# Drivers.net
KiCad netlist of a schematic drawn in Altium Designer
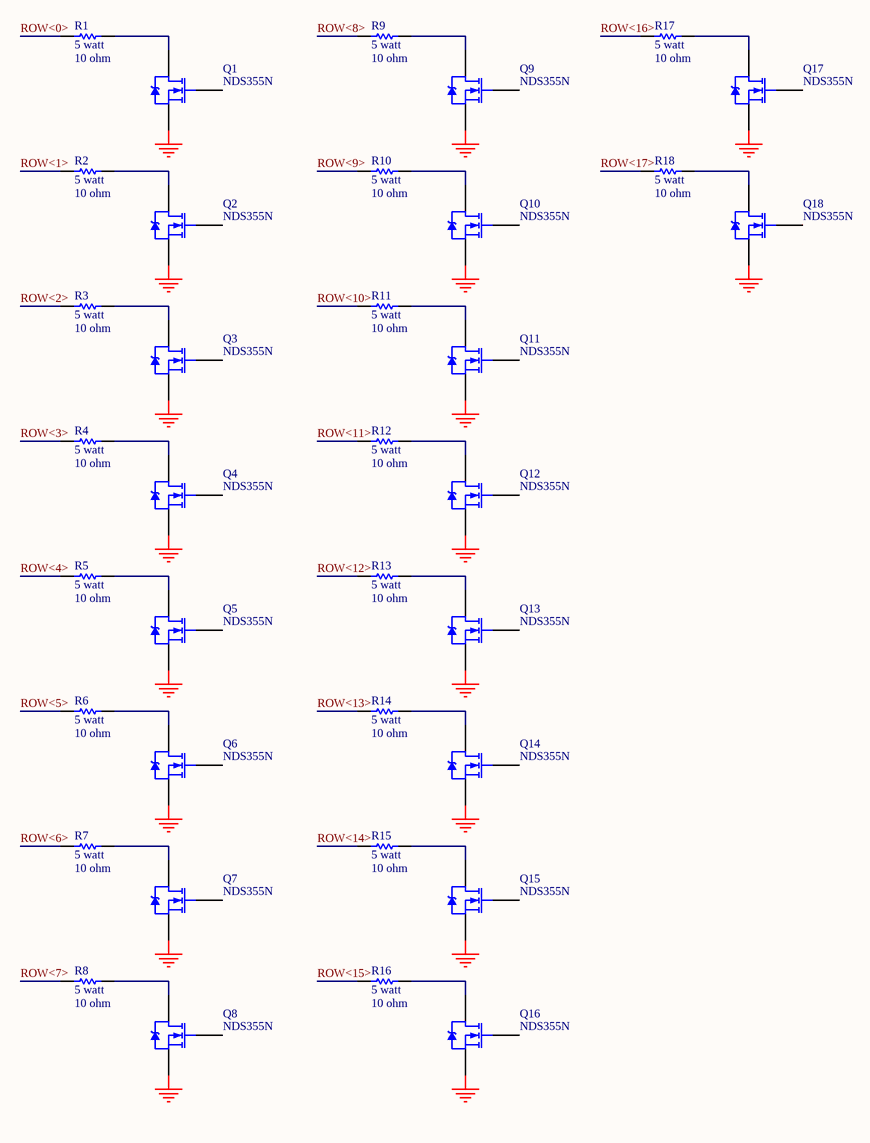
[diagram p0: Drivers.SchDoc]

(export (version "E")
  (design (tool "Eeschema 10.0.6"))
  (components
    (comp (ref "Q1")
      (value "NDS355N")
      (footprint "SO-G3")
      (description "N-Channel Logic Level Enhancement Mode FET")
      (fields (field (name "MANUFACTURER") "Fairchild"))
      (libsource (lib "Schlib1") (part "NDS355N"))
    )
    (comp (ref "Q2")
      (value "NDS355N")
      (footprint "SO-G3")
      (description "N-Channel Logic Level Enhancement Mode FET")
      (fields (field (name "MANUFACTURER") "Fairchild"))
      (libsource (lib "Schlib1") (part "NDS355N"))
    )
    (comp (ref "Q3")
      (value "NDS355N")
      (footprint "SO-G3")
      (description "N-Channel Logic Level Enhancement Mode FET")
      (fields (field (name "MANUFACTURER") "Fairchild"))
      (libsource (lib "Schlib1") (part "NDS355N"))
    )
    (comp (ref "Q4")
      (value "NDS355N")
      (footprint "SO-G3")
      (description "N-Channel Logic Level Enhancement Mode FET")
      (fields (field (name "MANUFACTURER") "Fairchild"))
      (libsource (lib "Schlib1") (part "NDS355N"))
    )
    (comp (ref "Q5")
      (value "NDS355N")
      (footprint "SO-G3")
      (description "N-Channel Logic Level Enhancement Mode FET")
      (fields (field (name "MANUFACTURER") "Fairchild"))
      (libsource (lib "Schlib1") (part "NDS355N"))
    )
    (comp (ref "Q6")
      (value "NDS355N")
      (footprint "SO-G3")
      (description "N-Channel Logic Level Enhancement Mode FET")
      (fields (field (name "MANUFACTURER") "Fairchild"))
      (libsource (lib "Schlib1") (part "NDS355N"))
    )
    (comp (ref "Q7")
      (value "NDS355N")
      (footprint "SO-G3")
      (description "N-Channel Logic Level Enhancement Mode FET")
      (fields (field (name "MANUFACTURER") "Fairchild"))
      (libsource (lib "Schlib1") (part "NDS355N"))
    )
    (comp (ref "Q8")
      (value "NDS355N")
      (footprint "SO-G3")
      (description "N-Channel Logic Level Enhancement Mode FET")
      (fields (field (name "MANUFACTURER") "Fairchild"))
      (libsource (lib "Schlib1") (part "NDS355N"))
    )
    (comp (ref "Q9")
      (value "NDS355N")
      (footprint "SO-G3")
      (description "N-Channel Logic Level Enhancement Mode FET")
      (fields (field (name "MANUFACTURER") "Fairchild"))
      (libsource (lib "Schlib1") (part "NDS355N"))
    )
    (comp (ref "Q10")
      (value "NDS355N")
      (footprint "SO-G3")
      (description "N-Channel Logic Level Enhancement Mode FET")
      (fields (field (name "MANUFACTURER") "Fairchild"))
      (libsource (lib "Schlib1") (part "NDS355N"))
    )
    (comp (ref "Q11")
      (value "NDS355N")
      (footprint "SO-G3")
      (description "N-Channel Logic Level Enhancement Mode FET")
      (fields (field (name "MANUFACTURER") "Fairchild"))
      (libsource (lib "Schlib1") (part "NDS355N"))
    )
    (comp (ref "Q12")
      (value "NDS355N")
      (footprint "SO-G3")
      (description "N-Channel Logic Level Enhancement Mode FET")
      (fields (field (name "MANUFACTURER") "Fairchild"))
      (libsource (lib "Schlib1") (part "NDS355N"))
    )
    (comp (ref "Q13")
      (value "NDS355N")
      (footprint "SO-G3")
      (description "N-Channel Logic Level Enhancement Mode FET")
      (fields (field (name "MANUFACTURER") "Fairchild"))
      (libsource (lib "Schlib1") (part "NDS355N"))
    )
    (comp (ref "Q14")
      (value "NDS355N")
      (footprint "SO-G3")
      (description "N-Channel Logic Level Enhancement Mode FET")
      (fields (field (name "MANUFACTURER") "Fairchild"))
      (libsource (lib "Schlib1") (part "NDS355N"))
    )
    (comp (ref "Q15")
      (value "NDS355N")
      (footprint "SO-G3")
      (description "N-Channel Logic Level Enhancement Mode FET")
      (fields (field (name "MANUFACTURER") "Fairchild"))
      (libsource (lib "Schlib1") (part "NDS355N"))
    )
    (comp (ref "Q16")
      (value "NDS355N")
      (footprint "SO-G3")
      (description "N-Channel Logic Level Enhancement Mode FET")
      (fields (field (name "MANUFACTURER") "Fairchild"))
      (libsource (lib "Schlib1") (part "NDS355N"))
    )
    (comp (ref "Q17")
      (value "NDS355N")
      (footprint "SO-G3")
      (description "N-Channel Logic Level Enhancement Mode FET")
      (fields (field (name "MANUFACTURER") "Fairchild"))
      (libsource (lib "Schlib1") (part "NDS355N"))
    )
    (comp (ref "Q18")
      (value "NDS355N")
      (footprint "SO-G3")
      (description "N-Channel Logic Level Enhancement Mode FET")
      (fields (field (name "MANUFACTURER") "Fairchild"))
      (libsource (lib "Schlib1") (part "NDS355N"))
    )
    (comp (ref "R1")
      (value "5 watt")
      (footprint "AXIAL-1.0")
      (description "Resistor")
      (fields
        (field (name "MANUFACTURER") "Generic Components")
        (field (name "ALTIUM_VALUE") "10 ohm")
        (field (name "PUBLISHER") "Altium Limited")
      )
      (libsource (lib "Miscellaneous Devices") (part "Res1"))
    )
    (comp (ref "R2")
      (value "5 watt")
      (footprint "AXIAL-1.0")
      (description "Resistor")
      (fields
        (field (name "MANUFACTURER") "Generic Components")
        (field (name "ALTIUM_VALUE") "10 ohm")
        (field (name "PUBLISHER") "Altium Limited")
      )
      (libsource (lib "Miscellaneous Devices") (part "Res1"))
    )
    (comp (ref "R3")
      (value "5 watt")
      (footprint "AXIAL-1.0")
      (description "Resistor")
      (fields
        (field (name "MANUFACTURER") "Generic Components")
        (field (name "ALTIUM_VALUE") "10 ohm")
        (field (name "PUBLISHER") "Altium Limited")
      )
      (libsource (lib "Miscellaneous Devices") (part "Res1"))
    )
    (comp (ref "R4")
      (value "5 watt")
      (footprint "AXIAL-1.0")
      (description "Resistor")
      (fields
        (field (name "MANUFACTURER") "Generic Components")
        (field (name "ALTIUM_VALUE") "10 ohm")
        (field (name "PUBLISHER") "Altium Limited")
      )
      (libsource (lib "Miscellaneous Devices") (part "Res1"))
    )
    (comp (ref "R5")
      (value "5 watt")
      (footprint "AXIAL-1.0")
      (description "Resistor")
      (fields
        (field (name "MANUFACTURER") "Generic Components")
        (field (name "ALTIUM_VALUE") "10 ohm")
        (field (name "PUBLISHER") "Altium Limited")
      )
      (libsource (lib "Miscellaneous Devices") (part "Res1"))
    )
    (comp (ref "R6")
      (value "5 watt")
      (footprint "AXIAL-1.0")
      (description "Resistor")
      (fields
        (field (name "MANUFACTURER") "Generic Components")
        (field (name "ALTIUM_VALUE") "10 ohm")
        (field (name "PUBLISHER") "Altium Limited")
      )
      (libsource (lib "Miscellaneous Devices") (part "Res1"))
    )
    (comp (ref "R7")
      (value "5 watt")
      (footprint "AXIAL-1.0")
      (description "Resistor")
      (fields
        (field (name "MANUFACTURER") "Generic Components")
        (field (name "ALTIUM_VALUE") "10 ohm")
        (field (name "PUBLISHER") "Altium Limited")
      )
      (libsource (lib "Miscellaneous Devices") (part "Res1"))
    )
    (comp (ref "R8")
      (value "5 watt")
      (footprint "AXIAL-1.0")
      (description "Resistor")
      (fields
        (field (name "MANUFACTURER") "Generic Components")
        (field (name "ALTIUM_VALUE") "10 ohm")
        (field (name "PUBLISHER") "Altium Limited")
      )
      (libsource (lib "Miscellaneous Devices") (part "Res1"))
    )
    (comp (ref "R9")
      (value "5 watt")
      (footprint "AXIAL-1.0")
      (description "Resistor")
      (fields
        (field (name "MANUFACTURER") "Generic Components")
        (field (name "ALTIUM_VALUE") "10 ohm")
        (field (name "PUBLISHER") "Altium Limited")
      )
      (libsource (lib "Miscellaneous Devices") (part "Res1"))
    )
    (comp (ref "R10")
      (value "5 watt")
      (footprint "AXIAL-1.0")
      (description "Resistor")
      (fields
        (field (name "MANUFACTURER") "Generic Components")
        (field (name "ALTIUM_VALUE") "10 ohm")
        (field (name "PUBLISHER") "Altium Limited")
      )
      (libsource (lib "Miscellaneous Devices") (part "Res1"))
    )
    (comp (ref "R11")
      (value "5 watt")
      (footprint "AXIAL-1.0")
      (description "Resistor")
      (fields
        (field (name "MANUFACTURER") "Generic Components")
        (field (name "ALTIUM_VALUE") "10 ohm")
        (field (name "PUBLISHER") "Altium Limited")
      )
      (libsource (lib "Miscellaneous Devices") (part "Res1"))
    )
    (comp (ref "R12")
      (value "5 watt")
      (footprint "AXIAL-1.0")
      (description "Resistor")
      (fields
        (field (name "MANUFACTURER") "Generic Components")
        (field (name "ALTIUM_VALUE") "10 ohm")
        (field (name "PUBLISHER") "Altium Limited")
      )
      (libsource (lib "Miscellaneous Devices") (part "Res1"))
    )
    (comp (ref "R13")
      (value "5 watt")
      (footprint "AXIAL-1.0")
      (description "Resistor")
      (fields
        (field (name "MANUFACTURER") "Generic Components")
        (field (name "ALTIUM_VALUE") "10 ohm")
        (field (name "PUBLISHER") "Altium Limited")
      )
      (libsource (lib "Miscellaneous Devices") (part "Res1"))
    )
    (comp (ref "R14")
      (value "5 watt")
      (footprint "AXIAL-1.0")
      (description "Resistor")
      (fields
        (field (name "MANUFACTURER") "Generic Components")
        (field (name "ALTIUM_VALUE") "10 ohm")
        (field (name "PUBLISHER") "Altium Limited")
      )
      (libsource (lib "Miscellaneous Devices") (part "Res1"))
    )
    (comp (ref "R15")
      (value "5 watt")
      (footprint "AXIAL-1.0")
      (description "Resistor")
      (fields
        (field (name "MANUFACTURER") "Generic Components")
        (field (name "ALTIUM_VALUE") "10 ohm")
        (field (name "PUBLISHER") "Altium Limited")
      )
      (libsource (lib "Miscellaneous Devices") (part "Res1"))
    )
    (comp (ref "R16")
      (value "5 watt")
      (footprint "AXIAL-1.0")
      (description "Resistor")
      (fields
        (field (name "MANUFACTURER") "Generic Components")
        (field (name "ALTIUM_VALUE") "10 ohm")
        (field (name "PUBLISHER") "Altium Limited")
      )
      (libsource (lib "Miscellaneous Devices") (part "Res1"))
    )
    (comp (ref "R17")
      (value "5 watt")
      (footprint "AXIAL-1.0")
      (description "Resistor")
      (fields
        (field (name "MANUFACTURER") "Generic Components")
        (field (name "ALTIUM_VALUE") "10 ohm")
        (field (name "PUBLISHER") "Altium Limited")
      )
      (libsource (lib "Miscellaneous Devices") (part "Res1"))
    )
    (comp (ref "R18")
      (value "5 watt")
      (footprint "AXIAL-1.0")
      (description "Resistor")
      (fields
        (field (name "MANUFACTURER") "Generic Components")
        (field (name "ALTIUM_VALUE") "10 ohm")
        (field (name "PUBLISHER") "Altium Limited")
      )
      (libsource (lib "Miscellaneous Devices") (part "Res1"))
    )
  )
  (nets
    (net (code "1") (name "/ROW<0>") (class "Default")
      (node (ref "R1") (pin "1") (pinfunction "1_1") (pintype "passive"))
    )
    (net (code "2") (name "/ROW<1>") (class "Default")
      (node (ref "R2") (pin "1") (pinfunction "1_1") (pintype "passive"))
    )
    (net (code "3") (name "/ROW<2>") (class "Default")
      (node (ref "R3") (pin "1") (pinfunction "1_1") (pintype "passive"))
    )
    (net (code "4") (name "/ROW<3>") (class "Default")
      (node (ref "R4") (pin "1") (pinfunction "1_1") (pintype "passive"))
    )
    (net (code "5") (name "/ROW<4>") (class "Default")
      (node (ref "R5") (pin "1") (pinfunction "1_1") (pintype "passive"))
    )
    (net (code "6") (name "/ROW<5>") (class "Default")
      (node (ref "R6") (pin "1") (pinfunction "1_1") (pintype "passive"))
    )
    (net (code "7") (name "/ROW<6>") (class "Default")
      (node (ref "R7") (pin "1") (pinfunction "1_1") (pintype "passive"))
    )
    (net (code "8") (name "/ROW<7>") (class "Default")
      (node (ref "R8") (pin "1") (pinfunction "1_1") (pintype "passive"))
    )
    (net (code "9") (name "/ROW<8>") (class "Default")
      (node (ref "R9") (pin "1") (pinfunction "1_1") (pintype "passive"))
    )
    (net (code "10") (name "/ROW<9>") (class "Default")
      (node (ref "R10") (pin "1") (pinfunction "1_1") (pintype "passive"))
    )
    (net (code "11") (name "/ROW<10>") (class "Default")
      (node (ref "R11") (pin "1") (pinfunction "1_1") (pintype "passive"))
    )
    (net (code "12") (name "/ROW<11>") (class "Default")
      (node (ref "R12") (pin "1") (pinfunction "1_1") (pintype "passive"))
    )
    (net (code "13") (name "/ROW<12>") (class "Default")
      (node (ref "R13") (pin "1") (pinfunction "1_1") (pintype "passive"))
    )
    (net (code "14") (name "/ROW<13>") (class "Default")
      (node (ref "R14") (pin "1") (pinfunction "1_1") (pintype "passive"))
    )
    (net (code "15") (name "/ROW<14>") (class "Default")
      (node (ref "R15") (pin "1") (pinfunction "1_1") (pintype "passive"))
    )
    (net (code "16") (name "/ROW<15>") (class "Default")
      (node (ref "R16") (pin "1") (pinfunction "1_1") (pintype "passive"))
    )
    (net (code "17") (name "/ROW<16>") (class "Default")
      (node (ref "R17") (pin "1") (pinfunction "1_1") (pintype "passive"))
    )
    (net (code "18") (name "/ROW<17>") (class "Default")
      (node (ref "R18") (pin "1") (pinfunction "1_1") (pintype "passive"))
    )
    (net (code "19") (name "GND") (class "Default")
      (node (ref "Q1") (pin "2") (pinfunction "S_2") (pintype "passive"))
      (node (ref "Q10") (pin "2") (pinfunction "S_2") (pintype "passive"))
      (node (ref "Q11") (pin "2") (pinfunction "S_2") (pintype "passive"))
      (node (ref "Q12") (pin "2") (pinfunction "S_2") (pintype "passive"))
      (node (ref "Q13") (pin "2") (pinfunction "S_2") (pintype "passive"))
      (node (ref "Q14") (pin "2") (pinfunction "S_2") (pintype "passive"))
      (node (ref "Q15") (pin "2") (pinfunction "S_2") (pintype "passive"))
      (node (ref "Q16") (pin "2") (pinfunction "S_2") (pintype "passive"))
      (node (ref "Q17") (pin "2") (pinfunction "S_2") (pintype "passive"))
      (node (ref "Q18") (pin "2") (pinfunction "S_2") (pintype "passive"))
      (node (ref "Q2") (pin "2") (pinfunction "S_2") (pintype "passive"))
      (node (ref "Q3") (pin "2") (pinfunction "S_2") (pintype "passive"))
      (node (ref "Q4") (pin "2") (pinfunction "S_2") (pintype "passive"))
      (node (ref "Q5") (pin "2") (pinfunction "S_2") (pintype "passive"))
      (node (ref "Q6") (pin "2") (pinfunction "S_2") (pintype "passive"))
      (node (ref "Q7") (pin "2") (pinfunction "S_2") (pintype "passive"))
      (node (ref "Q8") (pin "2") (pinfunction "S_2") (pintype "passive"))
      (node (ref "Q9") (pin "2") (pinfunction "S_2") (pintype "passive"))
    )
    (net (code "20") (name "Net-(Q1-D)") (class "Default")
      (node (ref "Q1") (pin "3") (pinfunction "D_3") (pintype "passive"))
      (node (ref "R1") (pin "2") (pinfunction "2_2") (pintype "passive"))
    )
    (net (code "21") (name "Net-(Q2-D)") (class "Default")
      (node (ref "Q2") (pin "3") (pinfunction "D_3") (pintype "passive"))
      (node (ref "R2") (pin "2") (pinfunction "2_2") (pintype "passive"))
    )
    (net (code "22") (name "Net-(Q3-D)") (class "Default")
      (node (ref "Q3") (pin "3") (pinfunction "D_3") (pintype "passive"))
      (node (ref "R3") (pin "2") (pinfunction "2_2") (pintype "passive"))
    )
    (net (code "23") (name "Net-(Q4-D)") (class "Default")
      (node (ref "Q4") (pin "3") (pinfunction "D_3") (pintype "passive"))
      (node (ref "R4") (pin "2") (pinfunction "2_2") (pintype "passive"))
    )
    (net (code "24") (name "Net-(Q5-D)") (class "Default")
      (node (ref "Q5") (pin "3") (pinfunction "D_3") (pintype "passive"))
      (node (ref "R5") (pin "2") (pinfunction "2_2") (pintype "passive"))
    )
    (net (code "25") (name "Net-(Q6-D)") (class "Default")
      (node (ref "Q6") (pin "3") (pinfunction "D_3") (pintype "passive"))
      (node (ref "R6") (pin "2") (pinfunction "2_2") (pintype "passive"))
    )
    (net (code "26") (name "Net-(Q7-D)") (class "Default")
      (node (ref "Q7") (pin "3") (pinfunction "D_3") (pintype "passive"))
      (node (ref "R7") (pin "2") (pinfunction "2_2") (pintype "passive"))
    )
    (net (code "27") (name "Net-(Q8-D)") (class "Default")
      (node (ref "Q8") (pin "3") (pinfunction "D_3") (pintype "passive"))
      (node (ref "R8") (pin "2") (pinfunction "2_2") (pintype "passive"))
    )
    (net (code "28") (name "Net-(Q9-D)") (class "Default")
      (node (ref "Q9") (pin "3") (pinfunction "D_3") (pintype "passive"))
      (node (ref "R9") (pin "2") (pinfunction "2_2") (pintype "passive"))
    )
    (net (code "29") (name "Net-(Q10-D)") (class "Default")
      (node (ref "Q10") (pin "3") (pinfunction "D_3") (pintype "passive"))
      (node (ref "R10") (pin "2") (pinfunction "2_2") (pintype "passive"))
    )
    (net (code "30") (name "Net-(Q11-D)") (class "Default")
      (node (ref "Q11") (pin "3") (pinfunction "D_3") (pintype "passive"))
      (node (ref "R11") (pin "2") (pinfunction "2_2") (pintype "passive"))
    )
    (net (code "31") (name "Net-(Q12-D)") (class "Default")
      (node (ref "Q12") (pin "3") (pinfunction "D_3") (pintype "passive"))
      (node (ref "R12") (pin "2") (pinfunction "2_2") (pintype "passive"))
    )
    (net (code "32") (name "Net-(Q13-D)") (class "Default")
      (node (ref "Q13") (pin "3") (pinfunction "D_3") (pintype "passive"))
      (node (ref "R13") (pin "2") (pinfunction "2_2") (pintype "passive"))
    )
    (net (code "33") (name "Net-(Q14-D)") (class "Default")
      (node (ref "Q14") (pin "3") (pinfunction "D_3") (pintype "passive"))
      (node (ref "R14") (pin "2") (pinfunction "2_2") (pintype "passive"))
    )
    (net (code "34") (name "Net-(Q15-D)") (class "Default")
      (node (ref "Q15") (pin "3") (pinfunction "D_3") (pintype "passive"))
      (node (ref "R15") (pin "2") (pinfunction "2_2") (pintype "passive"))
    )
    (net (code "35") (name "Net-(Q16-D)") (class "Default")
      (node (ref "Q16") (pin "3") (pinfunction "D_3") (pintype "passive"))
      (node (ref "R16") (pin "2") (pinfunction "2_2") (pintype "passive"))
    )
    (net (code "36") (name "Net-(Q17-D)") (class "Default")
      (node (ref "Q17") (pin "3") (pinfunction "D_3") (pintype "passive"))
      (node (ref "R17") (pin "2") (pinfunction "2_2") (pintype "passive"))
    )
    (net (code "37") (name "Net-(Q18-D)") (class "Default")
      (node (ref "Q18") (pin "3") (pinfunction "D_3") (pintype "passive"))
      (node (ref "R18") (pin "2") (pinfunction "2_2") (pintype "passive"))
    )
    (net (code "38") (name "unconnected-(Q1-G-Pad1)") (class "Default")
      (node (ref "Q1") (pin "1") (pinfunction "G_1") (pintype "passive"))
    )
    (net (code "39") (name "unconnected-(Q2-G-Pad1)") (class "Default")
      (node (ref "Q2") (pin "1") (pinfunction "G_1") (pintype "passive"))
    )
    (net (code "40") (name "unconnected-(Q3-G-Pad1)") (class "Default")
      (node (ref "Q3") (pin "1") (pinfunction "G_1") (pintype "passive"))
    )
    (net (code "41") (name "unconnected-(Q4-G-Pad1)") (class "Default")
      (node (ref "Q4") (pin "1") (pinfunction "G_1") (pintype "passive"))
    )
    (net (code "42") (name "unconnected-(Q5-G-Pad1)") (class "Default")
      (node (ref "Q5") (pin "1") (pinfunction "G_1") (pintype "passive"))
    )
    (net (code "43") (name "unconnected-(Q6-G-Pad1)") (class "Default")
      (node (ref "Q6") (pin "1") (pinfunction "G_1") (pintype "passive"))
    )
    (net (code "44") (name "unconnected-(Q7-G-Pad1)") (class "Default")
      (node (ref "Q7") (pin "1") (pinfunction "G_1") (pintype "passive"))
    )
    (net (code "45") (name "unconnected-(Q8-G-Pad1)") (class "Default")
      (node (ref "Q8") (pin "1") (pinfunction "G_1") (pintype "passive"))
    )
    (net (code "46") (name "unconnected-(Q9-G-Pad1)") (class "Default")
      (node (ref "Q9") (pin "1") (pinfunction "G_1") (pintype "passive"))
    )
    (net (code "47") (name "unconnected-(Q10-G-Pad1)") (class "Default")
      (node (ref "Q10") (pin "1") (pinfunction "G_1") (pintype "passive"))
    )
    (net (code "48") (name "unconnected-(Q11-G-Pad1)") (class "Default")
      (node (ref "Q11") (pin "1") (pinfunction "G_1") (pintype "passive"))
    )
    (net (code "49") (name "unconnected-(Q12-G-Pad1)") (class "Default")
      (node (ref "Q12") (pin "1") (pinfunction "G_1") (pintype "passive"))
    )
    (net (code "50") (name "unconnected-(Q13-G-Pad1)") (class "Default")
      (node (ref "Q13") (pin "1") (pinfunction "G_1") (pintype "passive"))
    )
    (net (code "51") (name "unconnected-(Q14-G-Pad1)") (class "Default")
      (node (ref "Q14") (pin "1") (pinfunction "G_1") (pintype "passive"))
    )
    (net (code "52") (name "unconnected-(Q15-G-Pad1)") (class "Default")
      (node (ref "Q15") (pin "1") (pinfunction "G_1") (pintype "passive"))
    )
    (net (code "53") (name "unconnected-(Q16-G-Pad1)") (class "Default")
      (node (ref "Q16") (pin "1") (pinfunction "G_1") (pintype "passive"))
    )
    (net (code "54") (name "unconnected-(Q17-G-Pad1)") (class "Default")
      (node (ref "Q17") (pin "1") (pinfunction "G_1") (pintype "passive"))
    )
    (net (code "55") (name "unconnected-(Q18-G-Pad1)") (class "Default")
      (node (ref "Q18") (pin "1") (pinfunction "G_1") (pintype "passive"))
    )
  )
)
